# remote.net
KiCad netlist of a schematic drawn in EAGLE
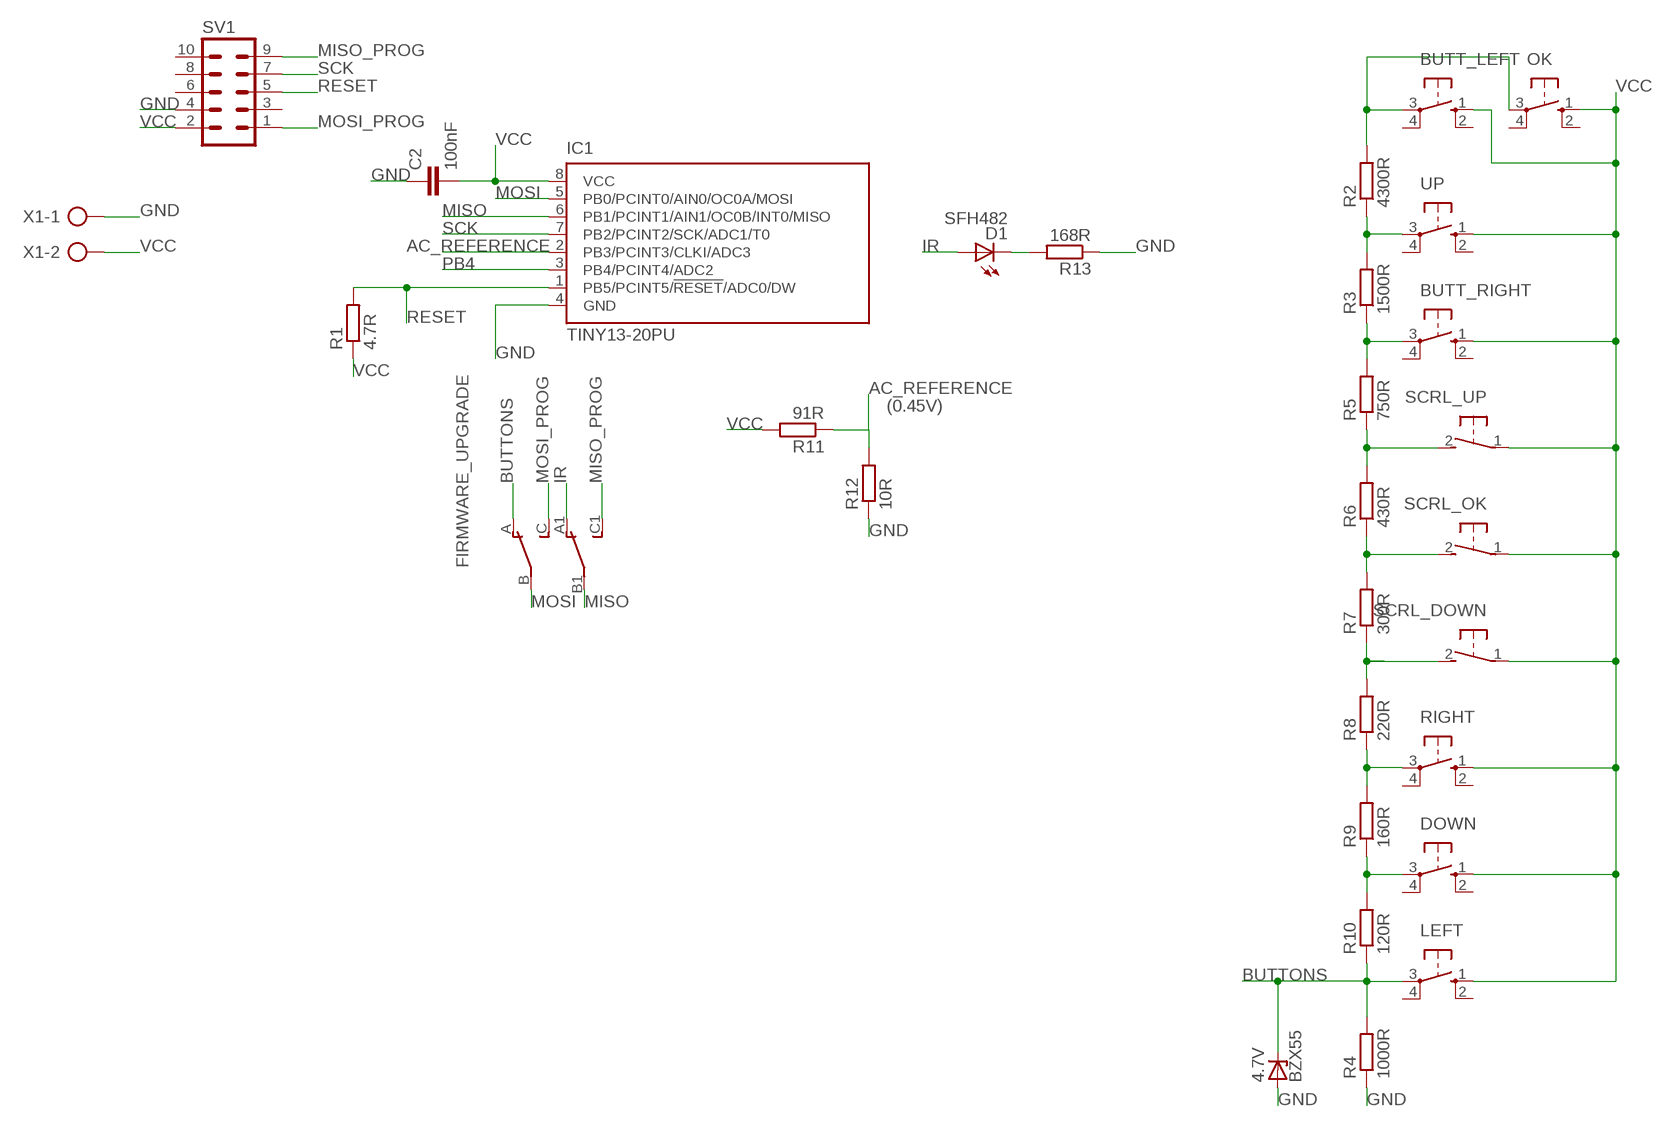
[diagram p0: schematic, sheet 1]

(export (version "E")
  (design (tool "Eeschema 10.0.6"))
  (components
    (comp (ref "4.7V")
      (value "BZX55")
      (footprint "eagle-import:DO35Z10")
      (libsource (lib "eagle-import") (part "BZX55"))
    )
    (comp (ref "BUTT_LEFT")
      (value "10-XX")
      (footprint "eagle-import:B3F-10XX")
      (fields (field (name "MPN") "B3F-1000"))
      (libsource (lib "eagle-import") (part "10-XX"))
    )
    (comp (ref "BUTT_RIGHT")
      (value "10-XX")
      (footprint "eagle-import:B3F-10XX")
      (fields
        (field (name "MPN") "B3F-1000")
        (field (name "MPN_1") "B3F-1000")
        (field (name "OC_FARNELL") "176432")
        (field (name "OC_NEWARK") "36M3542")
      )
      (libsource (lib "eagle-import") (part "10-XX"))
    )
    (comp (ref "C2")
      (value "100nF")
      (footprint "eagle-import:C050-024X044")
      (libsource (lib "eagle-import") (part "C-EU050-024X044"))
    )
    (comp (ref "D1")
      (value "SFH482")
      (footprint "eagle-import:SFH482")
      (libsource (lib "eagle-import") (part "SFH482"))
    )
    (comp (ref "DOWN")
      (value "10-XX")
      (footprint "eagle-import:B3F-10XX")
      (fields
        (field (name "MPN") "B3F-1000")
        (field (name "MPN_1") "B3F-1000")
        (field (name "OC_FARNELL") "176432")
        (field (name "OC_NEWARK") "36M3542")
      )
      (libsource (lib "eagle-import") (part "10-XX"))
    )
    (comp (ref "FIRMWARE_UPGRADE")
      (value "MINI_SLIDING_SWITCHS")
      (footprint "eagle-import:MINI_SLIDING_SWITCH")
      (libsource (lib "eagle-import") (part "MINI_SLIDING_SWITCHS"))
    )
    (comp (ref "IC1")
      (value "TINY13-20PU")
      (footprint "eagle-import:DIL08")
      (fields (field (name "MPN") "ATTINY13-20PU"))
      (libsource (lib "eagle-import") (part "TINY13PU-20"))
    )
    (comp (ref "LEFT")
      (value "10-XX")
      (footprint "eagle-import:B3F-10XX")
      (fields (field (name "MPN") "B3F-1000"))
      (libsource (lib "eagle-import") (part "10-XX"))
    )
    (comp (ref "OK")
      (value "10-XX")
      (footprint "eagle-import:B3F-10XX")
      (fields
        (field (name "MPN") "B3F-1000")
        (field (name "MPN_1") "B3F-1000")
        (field (name "OC_FARNELL") "176432")
        (field (name "OC_NEWARK") "36M3542")
      )
      (libsource (lib "eagle-import") (part "10-XX"))
    )
    (comp (ref "R1")
      (value "4.7R")
      (footprint "eagle-import:0204_7")
      (libsource (lib "eagle-import") (part "resistor_R-EU_0204/7"))
    )
    (comp (ref "R2")
      (value "4300R")
      (footprint "eagle-import:0204_7")
      (libsource (lib "eagle-import") (part "R-EU_0204/7"))
    )
    (comp (ref "R3")
      (value "1500R")
      (footprint "eagle-import:0204_7")
      (libsource (lib "eagle-import") (part "R-EU_0204/7"))
    )
    (comp (ref "R4")
      (value "1000R")
      (footprint "eagle-import:0204_7")
      (libsource (lib "eagle-import") (part "R-EU_0204/7"))
    )
    (comp (ref "R5")
      (value "750R")
      (footprint "eagle-import:0204_7")
      (libsource (lib "eagle-import") (part "R-EU_0204/7"))
    )
    (comp (ref "R6")
      (value "430R")
      (footprint "eagle-import:0204_7")
      (libsource (lib "eagle-import") (part "R-EU_0204/7"))
    )
    (comp (ref "R7")
      (value "300R")
      (footprint "eagle-import:0204_7")
      (libsource (lib "eagle-import") (part "R-EU_0204/7"))
    )
    (comp (ref "R8")
      (value "220R")
      (footprint "eagle-import:0204_7")
      (libsource (lib "eagle-import") (part "R-EU_0204/7"))
    )
    (comp (ref "R9")
      (value "160R")
      (footprint "eagle-import:0204_7")
      (libsource (lib "eagle-import") (part "R-EU_0204/7"))
    )
    (comp (ref "R10")
      (value "120R")
      (footprint "eagle-import:0204_7")
      (libsource (lib "eagle-import") (part "R-EU_0204/7"))
    )
    (comp (ref "R11")
      (value "91R")
      (footprint "eagle-import:0204_7")
      (libsource (lib "eagle-import") (part "R-EU_0204/7"))
    )
    (comp (ref "R12")
      (value "10R")
      (footprint "eagle-import:0204_7")
      (libsource (lib "eagle-import") (part "R-EU_0204/7"))
    )
    (comp (ref "R13")
      (value "168R")
      (footprint "eagle-import:0204_7")
      (libsource (lib "eagle-import") (part "R-EU_0204/7"))
    )
    (comp (ref "RIGHT")
      (value "10-XX")
      (footprint "eagle-import:B3F-10XX")
      (fields
        (field (name "MPN") "B3F-1000")
        (field (name "MPN_1") "B3F-1000")
        (field (name "OC_FARNELL") "176432")
        (field (name "OC_NEWARK") "36M3542")
      )
      (libsource (lib "eagle-import") (part "10-XX"))
    )
    (comp (ref "SCRL_DOWN")
      (value "31-XX")
      (footprint "eagle-import:B3F-31XX")
      (fields
        (field (name "MPN") "B3F-3100")
        (field (name "MPN_1") "B3F-3100")
        (field (name "OC_FARNELL") "959704")
        (field (name "OC_NEWARK") "36M3582")
      )
      (libsource (lib "eagle-import") (part "31-XX"))
    )
    (comp (ref "SCRL_OK")
      (value "31-XX")
      (footprint "eagle-import:B3F-31XX")
      (fields
        (field (name "MPN") "B3F-3100")
        (field (name "MPN_1") "B3F-3100")
        (field (name "OC_FARNELL") "959704")
        (field (name "OC_NEWARK") "36M3582")
      )
      (libsource (lib "eagle-import") (part "31-XX"))
    )
    (comp (ref "SCRL_UP")
      (value "31-XX")
      (footprint "eagle-import:B3F-31XX")
      (fields (field (name "MPN") "B3F-3100"))
      (libsource (lib "eagle-import") (part "31-XX"))
    )
    (comp (ref "SV1")
      (value "ML10L")
      (footprint "eagle-import:ML10L")
      (libsource (lib "eagle-import") (part "ML10L"))
    )
    (comp (ref "UP")
      (value "10-XX")
      (footprint "eagle-import:B3F-10XX")
      (fields
        (field (name "MPN") "B3F-1000")
        (field (name "MPN_1") "B3F-1000")
        (field (name "OC_FARNELL") "176432")
        (field (name "OC_NEWARK") "36M3542")
      )
      (libsource (lib "eagle-import") (part "10-XX"))
    )
    (comp (ref "X1")
      (value "AK300/2")
      (footprint "eagle-import:AK300_2")
      (libsource (lib "eagle-import") (part "AK300/2"))
    )
  )
  (nets
    (net (code "1") (name "/AC_REFERENCE") (class "Default")
      (node (ref "IC1") (pin "2") (pinfunction "PB3/PCINT3/CLKI/ADC3_2") (pintype "bidirectional"))
      (node (ref "R11") (pin "1") (pinfunction "1_1") (pintype "passive"))
      (node (ref "R12") (pin "2") (pinfunction "2_2") (pintype "passive"))
    )
    (net (code "2") (name "/BUTTONS") (class "Default")
      (node (ref "4.7V") (pin "C") (pinfunction "C_C") (pintype "passive"))
      (node (ref "FIRMWARE_UPGRADE") (pin "A") (pinfunction "A_A") (pintype "passive"))
      (node (ref "LEFT") (pin "3") (pinfunction "P_3") (pintype "passive"))
      (node (ref "R10") (pin "1") (pinfunction "1_1") (pintype "passive"))
      (node (ref "R4") (pin "2") (pinfunction "2_2") (pintype "passive"))
    )
    (net (code "3") (name "/GND") (class "Default")
      (node (ref "4.7V") (pin "A") (pinfunction "A_A") (pintype "passive"))
      (node (ref "C2") (pin "1") (pinfunction "1_1") (pintype "passive"))
      (node (ref "IC1") (pin "4") (pinfunction "GND_4") (pintype "power_in"))
      (node (ref "R12") (pin "1") (pinfunction "1_1") (pintype "passive"))
      (node (ref "R13") (pin "1") (pinfunction "1_1") (pintype "passive"))
      (node (ref "R4") (pin "1") (pinfunction "1_1") (pintype "passive"))
      (node (ref "SV1") (pin "4") (pinfunction "4_4") (pintype "passive"))
      (node (ref "X1") (pin "1") (pinfunction "KL_1") (pintype "passive"))
    )
    (net (code "4") (name "/IR") (class "Default")
      (node (ref "D1") (pin "A") (pinfunction "A_A") (pintype "passive"))
      (node (ref "FIRMWARE_UPGRADE") (pin "A1") (pinfunction "A1_A1") (pintype "passive"))
    )
    (net (code "5") (name "/MISO") (class "Default")
      (node (ref "FIRMWARE_UPGRADE") (pin "B1") (pinfunction "B1_B1") (pintype "passive"))
      (node (ref "IC1") (pin "6") (pinfunction "PB1/PCINT1/AIN1/OC0B/INT0/MISO_6") (pintype "bidirectional"))
    )
    (net (code "6") (name "/MISO_PROG") (class "Default")
      (node (ref "FIRMWARE_UPGRADE") (pin "C1") (pinfunction "C1_C1") (pintype "passive"))
      (node (ref "SV1") (pin "9") (pinfunction "9_9") (pintype "passive"))
    )
    (net (code "7") (name "/MOSI") (class "Default")
      (node (ref "FIRMWARE_UPGRADE") (pin "B") (pinfunction "B_B") (pintype "passive"))
      (node (ref "IC1") (pin "5") (pinfunction "PB0/PCINT0/AIN0/OC0A/MOSI_5") (pintype "bidirectional"))
    )
    (net (code "8") (name "/MOSI_PROG") (class "Default")
      (node (ref "FIRMWARE_UPGRADE") (pin "C") (pinfunction "C_C") (pintype "passive"))
      (node (ref "SV1") (pin "1") (pinfunction "1_1") (pintype "passive"))
    )
    (net (code "9") (name "/PB4") (class "Default")
      (node (ref "IC1") (pin "3") (pinfunction "PB4/PCINT4/ADC2_3") (pintype "bidirectional"))
    )
    (net (code "10") (name "/RESET") (class "Default")
      (node (ref "IC1") (pin "1") (pinfunction "PB5/PCINT5/~{RESET}/ADC0/DW_1") (pintype "bidirectional"))
      (node (ref "R1") (pin "2") (pinfunction "2_2") (pintype "passive"))
      (node (ref "SV1") (pin "5") (pinfunction "5_5") (pintype "passive"))
    )
    (net (code "11") (name "/SCK") (class "Default")
      (node (ref "IC1") (pin "7") (pinfunction "PB2/PCINT2/SCK/ADC1/T0_7") (pintype "bidirectional"))
      (node (ref "SV1") (pin "7") (pinfunction "7_7") (pintype "passive"))
    )
    (net (code "12") (name "/VCC") (class "Default")
      (node (ref "BUTT_LEFT") (pin "1") (pinfunction "S_1") (pintype "passive"))
      (node (ref "BUTT_RIGHT") (pin "1") (pinfunction "S_1") (pintype "passive"))
      (node (ref "C2") (pin "2") (pinfunction "2_2") (pintype "passive"))
      (node (ref "DOWN") (pin "1") (pinfunction "S_1") (pintype "passive"))
      (node (ref "IC1") (pin "8") (pinfunction "VCC_8") (pintype "power_in"))
      (node (ref "LEFT") (pin "1") (pinfunction "S_1") (pintype "passive"))
      (node (ref "OK") (pin "1") (pinfunction "S_1") (pintype "passive"))
      (node (ref "R1") (pin "1") (pinfunction "1_1") (pintype "passive"))
      (node (ref "R11") (pin "2") (pinfunction "2_2") (pintype "passive"))
      (node (ref "RIGHT") (pin "1") (pinfunction "S_1") (pintype "passive"))
      (node (ref "SCRL_DOWN") (pin "1") (pinfunction "P_1") (pintype "passive"))
      (node (ref "SCRL_OK") (pin "1") (pinfunction "P_1") (pintype "passive"))
      (node (ref "SCRL_UP") (pin "1") (pinfunction "P_1") (pintype "passive"))
      (node (ref "SV1") (pin "2") (pinfunction "2_2") (pintype "passive"))
      (node (ref "UP") (pin "1") (pinfunction "S_1") (pintype "passive"))
      (node (ref "X1") (pin "2") (pinfunction "KL_2") (pintype "passive"))
    )
    (net (code "13") (name "Net-(BUTT_LEFT-P)") (class "Default")
      (node (ref "BUTT_LEFT") (pin "3") (pinfunction "P_3") (pintype "passive"))
      (node (ref "OK") (pin "3") (pinfunction "P_3") (pintype "passive"))
      (node (ref "R2") (pin "2") (pinfunction "2_2") (pintype "passive"))
    )
    (net (code "14") (name "Net-(BUTT_RIGHT-P)") (class "Default")
      (node (ref "BUTT_RIGHT") (pin "3") (pinfunction "P_3") (pintype "passive"))
      (node (ref "R3") (pin "1") (pinfunction "1_1") (pintype "passive"))
      (node (ref "R5") (pin "2") (pinfunction "2_2") (pintype "passive"))
    )
    (net (code "15") (name "Net-(D1-C)") (class "Default")
      (node (ref "D1") (pin "K") (pinfunction "C_K") (pintype "passive"))
      (node (ref "R13") (pin "2") (pinfunction "2_2") (pintype "passive"))
    )
    (net (code "16") (name "Net-(DOWN-P)") (class "Default")
      (node (ref "DOWN") (pin "3") (pinfunction "P_3") (pintype "passive"))
      (node (ref "R10") (pin "2") (pinfunction "2_2") (pintype "passive"))
      (node (ref "R9") (pin "1") (pinfunction "1_1") (pintype "passive"))
    )
    (net (code "17") (name "Net-(RIGHT-P)") (class "Default")
      (node (ref "R8") (pin "1") (pinfunction "1_1") (pintype "passive"))
      (node (ref "R9") (pin "2") (pinfunction "2_2") (pintype "passive"))
      (node (ref "RIGHT") (pin "3") (pinfunction "P_3") (pintype "passive"))
    )
    (net (code "18") (name "Net-(SCRL_DOWN-S)") (class "Default")
      (node (ref "R7") (pin "1") (pinfunction "1_1") (pintype "passive"))
      (node (ref "R8") (pin "2") (pinfunction "2_2") (pintype "passive"))
      (node (ref "SCRL_DOWN") (pin "2") (pinfunction "S_2") (pintype "passive"))
    )
    (net (code "19") (name "Net-(SCRL_OK-S)") (class "Default")
      (node (ref "R6") (pin "1") (pinfunction "1_1") (pintype "passive"))
      (node (ref "R7") (pin "2") (pinfunction "2_2") (pintype "passive"))
      (node (ref "SCRL_OK") (pin "2") (pinfunction "S_2") (pintype "passive"))
    )
    (net (code "20") (name "Net-(SCRL_UP-S)") (class "Default")
      (node (ref "R5") (pin "1") (pinfunction "1_1") (pintype "passive"))
      (node (ref "R6") (pin "2") (pinfunction "2_2") (pintype "passive"))
      (node (ref "SCRL_UP") (pin "2") (pinfunction "S_2") (pintype "passive"))
    )
    (net (code "21") (name "Net-(UP-P)") (class "Default")
      (node (ref "R2") (pin "1") (pinfunction "1_1") (pintype "passive"))
      (node (ref "R3") (pin "2") (pinfunction "2_2") (pintype "passive"))
      (node (ref "UP") (pin "3") (pinfunction "P_3") (pintype "passive"))
    )
    (net (code "22") (name "unconnected-(BUTT_LEFT-P1-Pad4)") (class "Default")
      (node (ref "BUTT_LEFT") (pin "4") (pinfunction "P1_4") (pintype "passive"))
    )
    (net (code "23") (name "unconnected-(BUTT_LEFT-S1-Pad2)") (class "Default")
      (node (ref "BUTT_LEFT") (pin "2") (pinfunction "S1_2") (pintype "passive"))
    )
    (net (code "24") (name "unconnected-(BUTT_RIGHT-P1-Pad4)") (class "Default")
      (node (ref "BUTT_RIGHT") (pin "4") (pinfunction "P1_4") (pintype "passive"))
    )
    (net (code "25") (name "unconnected-(BUTT_RIGHT-S1-Pad2)") (class "Default")
      (node (ref "BUTT_RIGHT") (pin "2") (pinfunction "S1_2") (pintype "passive"))
    )
    (net (code "26") (name "unconnected-(DOWN-P1-Pad4)") (class "Default")
      (node (ref "DOWN") (pin "4") (pinfunction "P1_4") (pintype "passive"))
    )
    (net (code "27") (name "unconnected-(DOWN-S1-Pad2)") (class "Default")
      (node (ref "DOWN") (pin "2") (pinfunction "S1_2") (pintype "passive"))
    )
    (net (code "28") (name "unconnected-(LEFT-P1-Pad4)") (class "Default")
      (node (ref "LEFT") (pin "4") (pinfunction "P1_4") (pintype "passive"))
    )
    (net (code "29") (name "unconnected-(LEFT-S1-Pad2)") (class "Default")
      (node (ref "LEFT") (pin "2") (pinfunction "S1_2") (pintype "passive"))
    )
    (net (code "30") (name "unconnected-(OK-P1-Pad4)") (class "Default")
      (node (ref "OK") (pin "4") (pinfunction "P1_4") (pintype "passive"))
    )
    (net (code "31") (name "unconnected-(OK-S1-Pad2)") (class "Default")
      (node (ref "OK") (pin "2") (pinfunction "S1_2") (pintype "passive"))
    )
    (net (code "32") (name "unconnected-(RIGHT-P1-Pad4)") (class "Default")
      (node (ref "RIGHT") (pin "4") (pinfunction "P1_4") (pintype "passive"))
    )
    (net (code "33") (name "unconnected-(RIGHT-S1-Pad2)") (class "Default")
      (node (ref "RIGHT") (pin "2") (pinfunction "S1_2") (pintype "passive"))
    )
    (net (code "34") (name "unconnected-(SV1-Pad3)") (class "Default")
      (node (ref "SV1") (pin "3") (pinfunction "3_3") (pintype "passive"))
    )
    (net (code "35") (name "unconnected-(SV1-Pad6)") (class "Default")
      (node (ref "SV1") (pin "6") (pinfunction "6_6") (pintype "passive"))
    )
    (net (code "36") (name "unconnected-(SV1-Pad8)") (class "Default")
      (node (ref "SV1") (pin "8") (pinfunction "8_8") (pintype "passive"))
    )
    (net (code "37") (name "unconnected-(SV1-Pad10)") (class "Default")
      (node (ref "SV1") (pin "10") (pinfunction "10_10") (pintype "passive"))
    )
    (net (code "38") (name "unconnected-(UP-P1-Pad4)") (class "Default")
      (node (ref "UP") (pin "4") (pinfunction "P1_4") (pintype "passive"))
    )
    (net (code "39") (name "unconnected-(UP-S1-Pad2)") (class "Default")
      (node (ref "UP") (pin "2") (pinfunction "S1_2") (pintype "passive"))
    )
  )
)
